# lednode3.net
KiCad netlist of a schematic drawn in EAGLE
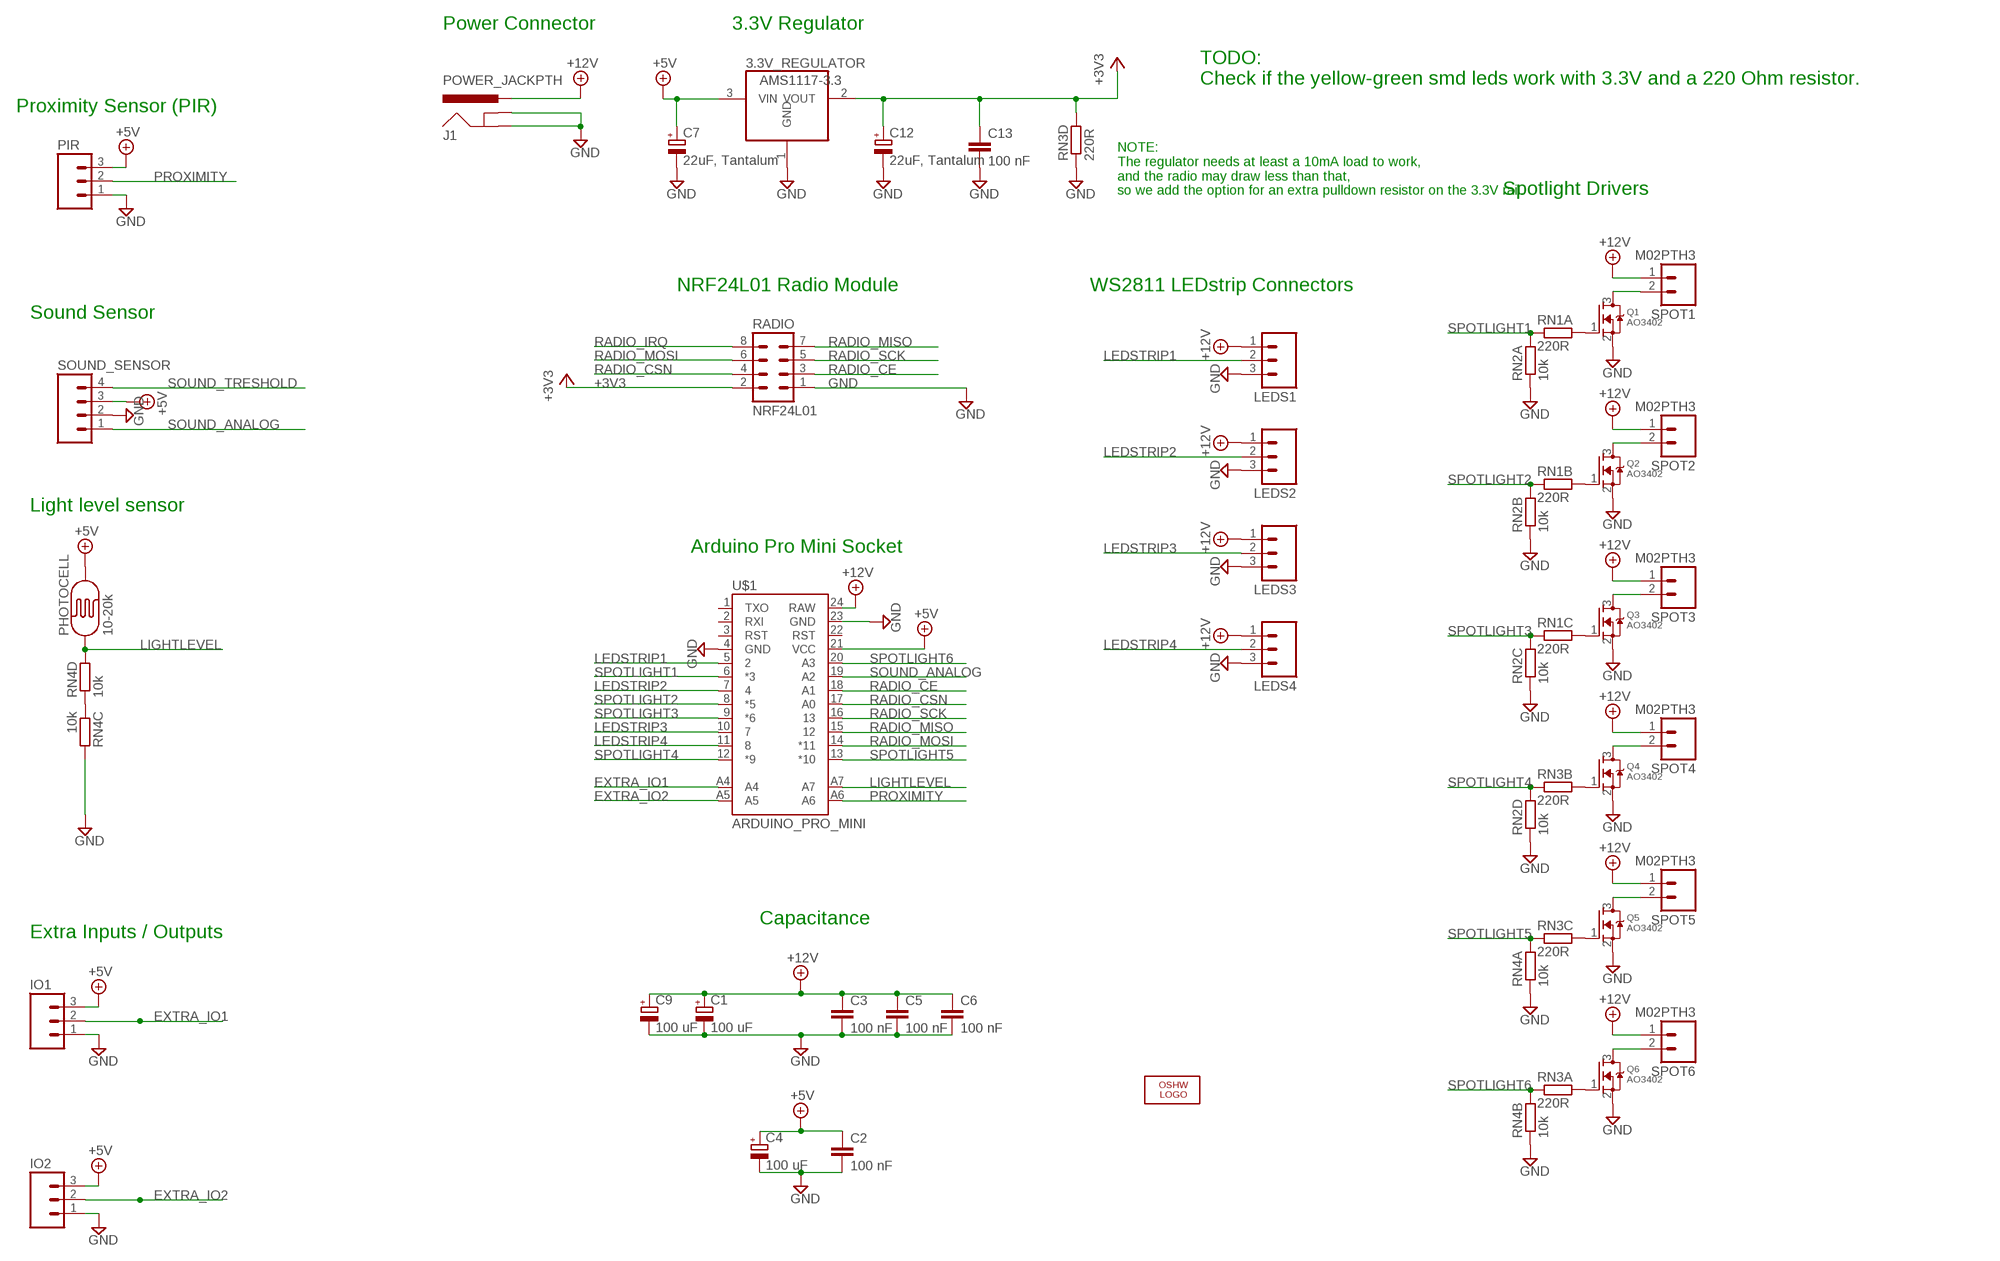
[diagram p0: schematic, sheet 1]

(export (version "E")
  (design (tool "Eeschema 10.0.6"))
  (components
    (comp (ref "3.3V_REGULATOR")
      (value "AMS1117-3.3")
      (footprint "eagle-import:SOT223")
      (fields (field (name "MPN") "REG1117"))
      (libsource (lib "eagle-import") (part "REG1117"))
    )
    (comp (ref "C1")
      (value "100 uF")
      (footprint "eagle-import:E2,5-6")
      (libsource (lib "eagle-import") (part "CPOL-EUE2.5-6"))
    )
    (comp (ref "C2")
      (value "100 nF")
      (footprint "eagle-import:C0805")
      (libsource (lib "eagle-import") (part "C-EUC0805"))
    )
    (comp (ref "C3")
      (value "100 nF")
      (footprint "eagle-import:C0805")
      (libsource (lib "eagle-import") (part "C-EUC0805"))
    )
    (comp (ref "C4")
      (value "100 uF")
      (footprint "eagle-import:E2,5-6")
      (libsource (lib "eagle-import") (part "CPOL-EUE2.5-6"))
    )
    (comp (ref "C5")
      (value "100 nF")
      (footprint "eagle-import:C0805")
      (libsource (lib "eagle-import") (part "C-EUC0805"))
    )
    (comp (ref "C6")
      (value "100 nF")
      (footprint "eagle-import:C0805")
      (libsource (lib "eagle-import") (part "C-EUC0805"))
    )
    (comp (ref "C7")
      (value "22uF, Tantalum")
      (footprint "eagle-import:SMC_A")
      (libsource (lib "eagle-import") (part "CPOL-EUSMCA"))
    )
    (comp (ref "C9")
      (value "100 uF")
      (footprint "eagle-import:E2,5-6")
      (libsource (lib "eagle-import") (part "CPOL-EUE2.5-6"))
    )
    (comp (ref "C12")
      (value "22uF, Tantalum")
      (footprint "eagle-import:SMC_A")
      (libsource (lib "eagle-import") (part "CPOL-EUSMCA"))
    )
    (comp (ref "C13")
      (value "100 nF")
      (footprint "eagle-import:C0805")
      (libsource (lib "eagle-import") (part "C-EUC0805"))
    )
    (comp (ref "IO1")
      (value "M03PTH")
      (footprint "eagle-import:1X03")
      (libsource (lib "eagle-import") (part "M03PTH"))
    )
    (comp (ref "IO2")
      (value "M03PTH")
      (footprint "eagle-import:1X03")
      (libsource (lib "eagle-import") (part "M03PTH"))
    )
    (comp (ref "J1")
      (value "POWER_JACKPTH")
      (footprint "eagle-import:POWER_JACK_PTH")
      (libsource (lib "eagle-import") (part "POWER_JACKPTH"))
    )
    (comp (ref "LEDS1")
      (value "M03LONGPADS")
      (footprint "eagle-import:1X03_LONGPADS")
      (libsource (lib "eagle-import") (part "M03LONGPADS"))
    )
    (comp (ref "LEDS2")
      (value "M03LONGPADS")
      (footprint "eagle-import:1X03_LONGPADS")
      (libsource (lib "eagle-import") (part "M03LONGPADS"))
    )
    (comp (ref "LEDS3")
      (value "M03LONGPADS")
      (footprint "eagle-import:1X03_LONGPADS")
      (libsource (lib "eagle-import") (part "M03LONGPADS"))
    )
    (comp (ref "LEDS4")
      (value "M03LONGPADS")
      (footprint "eagle-import:1X03_LONGPADS")
      (libsource (lib "eagle-import") (part "M03LONGPADS"))
    )
    (comp (ref "LOGO3")
      (value "LOGO-OSHW-8MILX0100-NT")
      (footprint "eagle-import:OSHW_8X100_NOTEXT")
      (libsource (lib "eagle-import") (part "LOGO-OSHW-8MILX0100-NT"))
    )
    (comp (ref "PHOTOCELL")
      (value "10-20k")
      (footprint "eagle-import:PHOTOCELL")
      (libsource (lib "eagle-import") (part "PHOTOCELLPTH"))
    )
    (comp (ref "PIR")
      (value "M03PTH")
      (footprint "eagle-import:1X03")
      (libsource (lib "eagle-import") (part "M03PTH"))
    )
    (comp (ref "Q1")
      (value "AO3402")
      (footprint "eagle-import:SOT23-W")
      (libsource (lib "eagle-import") (part "MOSFET-NWAVE"))
    )
    (comp (ref "Q2")
      (value "AO3402")
      (footprint "eagle-import:SOT23-W")
      (libsource (lib "eagle-import") (part "MOSFET-NWAVE"))
    )
    (comp (ref "Q3")
      (value "AO3402")
      (footprint "eagle-import:SOT23-W")
      (libsource (lib "eagle-import") (part "MOSFET-NWAVE"))
    )
    (comp (ref "Q4")
      (value "AO3402")
      (footprint "eagle-import:SOT23-W")
      (libsource (lib "eagle-import") (part "MOSFET-NWAVE"))
    )
    (comp (ref "Q5")
      (value "AO3402")
      (footprint "eagle-import:SOT23-W")
      (libsource (lib "eagle-import") (part "MOSFET-NWAVE"))
    )
    (comp (ref "Q6")
      (value "AO3402")
      (footprint "eagle-import:SOT23-W")
      (libsource (lib "eagle-import") (part "MOSFET-NWAVE"))
    )
    (comp (ref "RADIO")
      (value "NRF24L01")
      (footprint "eagle-import:MA04-2")
      (libsource (lib "eagle-import") (part "MA04-2"))
    )
    (comp (ref "RN1")
      (value "220R")
      (footprint "eagle-import:RN8P-4R-CRA06S")
      (libsource (lib "eagle-import") (part "RESISTOR_ARRAY_4"))
    )
    (comp (ref "RN2")
      (value "10k")
      (footprint "eagle-import:RN8P-4R-CRA06S")
      (libsource (lib "eagle-import") (part "RESISTOR_ARRAY_4"))
    )
    (comp (ref "RN3")
      (value "220R")
      (footprint "eagle-import:RN8P-4R-CRA06S")
      (libsource (lib "eagle-import") (part "RESISTOR_ARRAY_4"))
    )
    (comp (ref "RN4")
      (value "10k")
      (footprint "eagle-import:RN8P-4R-CRA06S")
      (libsource (lib "eagle-import") (part "RESISTOR_ARRAY_4"))
    )
    (comp (ref "SOUND_SENSOR")
      (value "M041X04_NO_SILK")
      (footprint "eagle-import:1X04_NO_SILK")
      (libsource (lib "eagle-import") (part "M041X04_NO_SILK"))
    )
    (comp (ref "SPOT1")
      (value "M02PTH3")
      (footprint "eagle-import:1X02_LONGPADS")
      (libsource (lib "eagle-import") (part "M02PTH3"))
    )
    (comp (ref "SPOT2")
      (value "M02PTH3")
      (footprint "eagle-import:1X02_LONGPADS")
      (libsource (lib "eagle-import") (part "M02PTH3"))
    )
    (comp (ref "SPOT3")
      (value "M02PTH3")
      (footprint "eagle-import:1X02_LONGPADS")
      (libsource (lib "eagle-import") (part "M02PTH3"))
    )
    (comp (ref "SPOT4")
      (value "M02PTH3")
      (footprint "eagle-import:1X02_LONGPADS")
      (libsource (lib "eagle-import") (part "M02PTH3"))
    )
    (comp (ref "SPOT5")
      (value "M02PTH3")
      (footprint "eagle-import:1X02_LONGPADS")
      (libsource (lib "eagle-import") (part "M02PTH3"))
    )
    (comp (ref "SPOT6")
      (value "M02PTH3")
      (footprint "eagle-import:1X02_LONGPADS")
      (libsource (lib "eagle-import") (part "M02PTH3"))
    )
    (comp (ref "U$1")
      (value "ARDUINO_PRO_MINI")
      (footprint "eagle-import:ARDUINO_PRO_MINI")
      (libsource (lib "eagle-import") (part "ARDUINO_PRO_MINI"))
    )
  )
  (nets
    (net (code "1") (name "+3V3") (class "Default")
      (node (ref "3.3V_REGULATOR") (pin "2") (pinfunction "VOUT_2") (pintype "output"))
      (node (ref "C12") (pin "+") (pinfunction "+_+") (pintype "passive"))
      (node (ref "C13") (pin "1") (pinfunction "1_1") (pintype "passive"))
      (node (ref "RADIO") (pin "2") (pinfunction "2_2") (pintype "passive"))
      (node (ref "RN3") (pin "5") (pinfunction "2_5") (pintype "passive"))
    )
    (net (code "2") (name "+5V") (class "Default")
      (node (ref "3.3V_REGULATOR") (pin "3") (pinfunction "VIN_3") (pintype "input"))
      (node (ref "C2") (pin "1") (pinfunction "1_1") (pintype "passive"))
      (node (ref "C4") (pin "+") (pinfunction "+_+") (pintype "passive"))
      (node (ref "C7") (pin "+") (pinfunction "+_+") (pintype "passive"))
      (node (ref "IO1") (pin "3") (pinfunction "3_3") (pintype "passive"))
      (node (ref "IO2") (pin "3") (pinfunction "3_3") (pintype "passive"))
      (node (ref "PHOTOCELL") (pin "2") (pinfunction "P$2_2") (pintype "bidirectional"))
      (node (ref "PIR") (pin "3") (pinfunction "3_3") (pintype "passive"))
      (node (ref "SOUND_SENSOR") (pin "3") (pinfunction "3_3") (pintype "passive"))
      (node (ref "U$1") (pin "21") (pinfunction "VCC_21") (pintype "bidirectional"))
    )
    (net (code "3") (name "+12V") (class "Default")
      (node (ref "C1") (pin "+") (pinfunction "+_+") (pintype "passive"))
      (node (ref "C3") (pin "1") (pinfunction "1_1") (pintype "passive"))
      (node (ref "C5") (pin "1") (pinfunction "1_1") (pintype "passive"))
      (node (ref "C6") (pin "1") (pinfunction "1_1") (pintype "passive"))
      (node (ref "C9") (pin "+") (pinfunction "+_+") (pintype "passive"))
      (node (ref "J1") (pin "PWR") (pinfunction "PWR_PWR") (pintype "bidirectional"))
      (node (ref "LEDS1") (pin "1") (pinfunction "1_1") (pintype "passive"))
      (node (ref "LEDS2") (pin "1") (pinfunction "1_1") (pintype "passive"))
      (node (ref "LEDS3") (pin "1") (pinfunction "1_1") (pintype "passive"))
      (node (ref "LEDS4") (pin "1") (pinfunction "1_1") (pintype "passive"))
      (node (ref "SPOT1") (pin "1") (pinfunction "1_1") (pintype "passive"))
      (node (ref "SPOT2") (pin "1") (pinfunction "1_1") (pintype "passive"))
      (node (ref "SPOT3") (pin "1") (pinfunction "1_1") (pintype "passive"))
      (node (ref "SPOT4") (pin "1") (pinfunction "1_1") (pintype "passive"))
      (node (ref "SPOT5") (pin "1") (pinfunction "1_1") (pintype "passive"))
      (node (ref "SPOT6") (pin "1") (pinfunction "1_1") (pintype "passive"))
      (node (ref "U$1") (pin "24") (pinfunction "RAW_24") (pintype "bidirectional"))
    )
    (net (code "4") (name "/EXTRA_IO1") (class "Default")
      (node (ref "IO1") (pin "2") (pinfunction "2_2") (pintype "passive"))
      (node (ref "U$1") (pin "A4") (pinfunction "A4_A4") (pintype "bidirectional"))
    )
    (net (code "5") (name "/EXTRA_IO2") (class "Default")
      (node (ref "IO2") (pin "2") (pinfunction "2_2") (pintype "passive"))
      (node (ref "U$1") (pin "A5") (pinfunction "A5_A5") (pintype "bidirectional"))
    )
    (net (code "6") (name "/LEDSTRIP1") (class "Default")
      (node (ref "LEDS1") (pin "2") (pinfunction "2_2") (pintype "passive"))
      (node (ref "U$1") (pin "5") (pinfunction "2_5") (pintype "bidirectional"))
    )
    (net (code "7") (name "/LEDSTRIP2") (class "Default")
      (node (ref "LEDS2") (pin "2") (pinfunction "2_2") (pintype "passive"))
      (node (ref "U$1") (pin "7") (pinfunction "4_7") (pintype "bidirectional"))
    )
    (net (code "8") (name "/LEDSTRIP3") (class "Default")
      (node (ref "LEDS3") (pin "2") (pinfunction "2_2") (pintype "passive"))
      (node (ref "U$1") (pin "10") (pinfunction "7_10") (pintype "bidirectional"))
    )
    (net (code "9") (name "/LEDSTRIP4") (class "Default")
      (node (ref "LEDS4") (pin "2") (pinfunction "2_2") (pintype "passive"))
      (node (ref "U$1") (pin "11") (pinfunction "8_11") (pintype "bidirectional"))
    )
    (net (code "10") (name "/LIGHTLEVEL") (class "Default")
      (node (ref "PHOTOCELL") (pin "1") (pinfunction "P$1_1") (pintype "bidirectional"))
      (node (ref "RN4") (pin "5") (pinfunction "2_5") (pintype "passive"))
      (node (ref "U$1") (pin "A7") (pinfunction "A7_A7") (pintype "bidirectional"))
    )
    (net (code "11") (name "/PROXIMITY") (class "Default")
      (node (ref "PIR") (pin "2") (pinfunction "2_2") (pintype "passive"))
      (node (ref "U$1") (pin "A6") (pinfunction "A6_A6") (pintype "bidirectional"))
    )
    (net (code "12") (name "/RADIO_CE") (class "Default")
      (node (ref "RADIO") (pin "3") (pinfunction "3_3") (pintype "passive"))
      (node (ref "U$1") (pin "18") (pinfunction "A1_18") (pintype "bidirectional"))
    )
    (net (code "13") (name "/RADIO_CSN") (class "Default")
      (node (ref "RADIO") (pin "4") (pinfunction "4_4") (pintype "passive"))
      (node (ref "U$1") (pin "17") (pinfunction "A0_17") (pintype "bidirectional"))
    )
    (net (code "14") (name "/RADIO_IRQ") (class "Default")
      (node (ref "RADIO") (pin "8") (pinfunction "8_8") (pintype "passive"))
    )
    (net (code "15") (name "/RADIO_MISO") (class "Default")
      (node (ref "RADIO") (pin "7") (pinfunction "7_7") (pintype "passive"))
      (node (ref "U$1") (pin "15") (pinfunction "12_15") (pintype "bidirectional"))
    )
    (net (code "16") (name "/RADIO_MOSI") (class "Default")
      (node (ref "RADIO") (pin "6") (pinfunction "6_6") (pintype "passive"))
      (node (ref "U$1") (pin "14") (pinfunction "*11_14") (pintype "bidirectional"))
    )
    (net (code "17") (name "/RADIO_SCK") (class "Default")
      (node (ref "RADIO") (pin "5") (pinfunction "5_5") (pintype "passive"))
      (node (ref "U$1") (pin "16") (pinfunction "13_16") (pintype "bidirectional"))
    )
    (net (code "18") (name "/SOUND_ANALOG") (class "Default")
      (node (ref "SOUND_SENSOR") (pin "1") (pinfunction "1_1") (pintype "passive"))
      (node (ref "U$1") (pin "19") (pinfunction "A2_19") (pintype "bidirectional"))
    )
    (net (code "19") (name "/SOUND_TRESHOLD") (class "Default")
      (node (ref "SOUND_SENSOR") (pin "4") (pinfunction "4_4") (pintype "passive"))
    )
    (net (code "20") (name "/SPOTLIGHT1") (class "Default")
      (node (ref "RN1") (pin "1") (pinfunction "1_1") (pintype "passive"))
      (node (ref "RN2") (pin "8") (pinfunction "2_8") (pintype "passive"))
      (node (ref "U$1") (pin "6") (pinfunction "*3_6") (pintype "bidirectional"))
    )
    (net (code "21") (name "/SPOTLIGHT2") (class "Default")
      (node (ref "RN1") (pin "2") (pinfunction "1_2") (pintype "passive"))
      (node (ref "RN2") (pin "7") (pinfunction "2_7") (pintype "passive"))
      (node (ref "U$1") (pin "8") (pinfunction "*5_8") (pintype "bidirectional"))
    )
    (net (code "22") (name "/SPOTLIGHT3") (class "Default")
      (node (ref "RN1") (pin "3") (pinfunction "1_3") (pintype "passive"))
      (node (ref "RN2") (pin "6") (pinfunction "2_6") (pintype "passive"))
      (node (ref "U$1") (pin "9") (pinfunction "*6_9") (pintype "bidirectional"))
    )
    (net (code "23") (name "/SPOTLIGHT4") (class "Default")
      (node (ref "RN2") (pin "5") (pinfunction "2_5") (pintype "passive"))
      (node (ref "RN3") (pin "2") (pinfunction "1_2") (pintype "passive"))
      (node (ref "U$1") (pin "12") (pinfunction "*9_12") (pintype "bidirectional"))
    )
    (net (code "24") (name "/SPOTLIGHT5") (class "Default")
      (node (ref "RN3") (pin "3") (pinfunction "1_3") (pintype "passive"))
      (node (ref "RN4") (pin "8") (pinfunction "2_8") (pintype "passive"))
      (node (ref "U$1") (pin "13") (pinfunction "*10_13") (pintype "bidirectional"))
    )
    (net (code "25") (name "/SPOTLIGHT6") (class "Default")
      (node (ref "RN3") (pin "1") (pinfunction "1_1") (pintype "passive"))
      (node (ref "RN4") (pin "7") (pinfunction "2_7") (pintype "passive"))
      (node (ref "U$1") (pin "20") (pinfunction "A3_20") (pintype "bidirectional"))
    )
    (net (code "26") (name "GND") (class "Default")
      (node (ref "3.3V_REGULATOR") (pin "1") (pinfunction "GND_1") (pintype "power_in"))
      (node (ref "C1") (pin "-") (pinfunction "-_-") (pintype "passive"))
      (node (ref "C12") (pin "-") (pinfunction "-_-") (pintype "passive"))
      (node (ref "C13") (pin "2") (pinfunction "2_2") (pintype "passive"))
      (node (ref "C2") (pin "2") (pinfunction "2_2") (pintype "passive"))
      (node (ref "C3") (pin "2") (pinfunction "2_2") (pintype "passive"))
      (node (ref "C4") (pin "-") (pinfunction "-_-") (pintype "passive"))
      (node (ref "C5") (pin "2") (pinfunction "2_2") (pintype "passive"))
      (node (ref "C6") (pin "2") (pinfunction "2_2") (pintype "passive"))
      (node (ref "C7") (pin "-") (pinfunction "-_-") (pintype "passive"))
      (node (ref "C9") (pin "-") (pinfunction "-_-") (pintype "passive"))
      (node (ref "IO1") (pin "1") (pinfunction "1_1") (pintype "passive"))
      (node (ref "IO2") (pin "1") (pinfunction "1_1") (pintype "passive"))
      (node (ref "J1") (pin "GND") (pinfunction "GND_GND") (pintype "bidirectional"))
      (node (ref "J1") (pin "GNDBREAK") (pinfunction "GNDBREAK_GNDBREAK") (pintype "bidirectional"))
      (node (ref "LEDS1") (pin "3") (pinfunction "3_3") (pintype "passive"))
      (node (ref "LEDS2") (pin "3") (pinfunction "3_3") (pintype "passive"))
      (node (ref "LEDS3") (pin "3") (pinfunction "3_3") (pintype "passive"))
      (node (ref "LEDS4") (pin "3") (pinfunction "3_3") (pintype "passive"))
      (node (ref "PIR") (pin "1") (pinfunction "1_1") (pintype "passive"))
      (node (ref "Q1") (pin "2") (pinfunction "S_2") (pintype "bidirectional"))
      (node (ref "Q2") (pin "2") (pinfunction "S_2") (pintype "bidirectional"))
      (node (ref "Q3") (pin "2") (pinfunction "S_2") (pintype "bidirectional"))
      (node (ref "Q4") (pin "2") (pinfunction "S_2") (pintype "bidirectional"))
      (node (ref "Q5") (pin "2") (pinfunction "S_2") (pintype "bidirectional"))
      (node (ref "Q6") (pin "2") (pinfunction "S_2") (pintype "bidirectional"))
      (node (ref "RADIO") (pin "1") (pinfunction "1_1") (pintype "passive"))
      (node (ref "RN2") (pin "1") (pinfunction "1_1") (pintype "passive"))
      (node (ref "RN2") (pin "2") (pinfunction "1_2") (pintype "passive"))
      (node (ref "RN2") (pin "3") (pinfunction "1_3") (pintype "passive"))
      (node (ref "RN2") (pin "4") (pinfunction "1_4") (pintype "passive"))
      (node (ref "RN3") (pin "4") (pinfunction "1_4") (pintype "passive"))
      (node (ref "RN4") (pin "1") (pinfunction "1_1") (pintype "passive"))
      (node (ref "RN4") (pin "2") (pinfunction "1_2") (pintype "passive"))
      (node (ref "RN4") (pin "6") (pinfunction "2_6") (pintype "passive"))
      (node (ref "SOUND_SENSOR") (pin "2") (pinfunction "2_2") (pintype "passive"))
      (node (ref "U$1") (pin "23") (pinfunction "GND_23") (pintype "bidirectional"))
      (node (ref "U$1") (pin "4") (pinfunction "GND_4") (pintype "bidirectional"))
    )
    (net (code "27") (name "Net-(Q1-D)") (class "Default")
      (node (ref "Q1") (pin "3") (pinfunction "D_3") (pintype "bidirectional"))
      (node (ref "SPOT1") (pin "2") (pinfunction "2_2") (pintype "passive"))
    )
    (net (code "28") (name "Net-(Q1-G)") (class "Default")
      (node (ref "Q1") (pin "1") (pinfunction "G_1") (pintype "bidirectional"))
      (node (ref "RN1") (pin "8") (pinfunction "2_8") (pintype "passive"))
    )
    (net (code "29") (name "Net-(Q2-D)") (class "Default")
      (node (ref "Q2") (pin "3") (pinfunction "D_3") (pintype "bidirectional"))
      (node (ref "SPOT2") (pin "2") (pinfunction "2_2") (pintype "passive"))
    )
    (net (code "30") (name "Net-(Q2-G)") (class "Default")
      (node (ref "Q2") (pin "1") (pinfunction "G_1") (pintype "bidirectional"))
      (node (ref "RN1") (pin "7") (pinfunction "2_7") (pintype "passive"))
    )
    (net (code "31") (name "Net-(Q3-D)") (class "Default")
      (node (ref "Q3") (pin "3") (pinfunction "D_3") (pintype "bidirectional"))
      (node (ref "SPOT3") (pin "2") (pinfunction "2_2") (pintype "passive"))
    )
    (net (code "32") (name "Net-(Q3-G)") (class "Default")
      (node (ref "Q3") (pin "1") (pinfunction "G_1") (pintype "bidirectional"))
      (node (ref "RN1") (pin "6") (pinfunction "2_6") (pintype "passive"))
    )
    (net (code "33") (name "Net-(Q4-D)") (class "Default")
      (node (ref "Q4") (pin "3") (pinfunction "D_3") (pintype "bidirectional"))
      (node (ref "SPOT4") (pin "2") (pinfunction "2_2") (pintype "passive"))
    )
    (net (code "34") (name "Net-(Q4-G)") (class "Default")
      (node (ref "Q4") (pin "1") (pinfunction "G_1") (pintype "bidirectional"))
      (node (ref "RN3") (pin "7") (pinfunction "2_7") (pintype "passive"))
    )
    (net (code "35") (name "Net-(Q5-D)") (class "Default")
      (node (ref "Q5") (pin "3") (pinfunction "D_3") (pintype "bidirectional"))
      (node (ref "SPOT5") (pin "2") (pinfunction "2_2") (pintype "passive"))
    )
    (net (code "36") (name "Net-(Q5-G)") (class "Default")
      (node (ref "Q5") (pin "1") (pinfunction "G_1") (pintype "bidirectional"))
      (node (ref "RN3") (pin "6") (pinfunction "2_6") (pintype "passive"))
    )
    (net (code "37") (name "Net-(Q6-D)") (class "Default")
      (node (ref "Q6") (pin "3") (pinfunction "D_3") (pintype "bidirectional"))
      (node (ref "SPOT6") (pin "2") (pinfunction "2_2") (pintype "passive"))
    )
    (net (code "38") (name "Net-(Q6-G)") (class "Default")
      (node (ref "Q6") (pin "1") (pinfunction "G_1") (pintype "bidirectional"))
      (node (ref "RN3") (pin "8") (pinfunction "2_8") (pintype "passive"))
    )
    (net (code "39") (name "Net-(RN4C-1)") (class "Default")
      (node (ref "RN4") (pin "3") (pinfunction "1_3") (pintype "passive"))
      (node (ref "RN4") (pin "4") (pinfunction "1_4") (pintype "passive"))
    )
    (net (code "40") (name "unconnected-(U$1-RST-Pad3)") (class "Default")
      (node (ref "U$1") (pin "3") (pinfunction "RST_3") (pintype "bidirectional"))
    )
    (net (code "41") (name "unconnected-(U$1-RST-Pad22)") (class "Default")
      (node (ref "U$1") (pin "22") (pinfunction "RST_22") (pintype "bidirectional"))
    )
    (net (code "42") (name "unconnected-(U$1-RXI-Pad2)") (class "Default")
      (node (ref "U$1") (pin "2") (pinfunction "RXI_2") (pintype "bidirectional"))
    )
    (net (code "43") (name "unconnected-(U$1-TXO-Pad1)") (class "Default")
      (node (ref "U$1") (pin "1") (pinfunction "TXO_1") (pintype "bidirectional"))
    )
  )
)
